# lmr14206.net
KiCad netlist of a schematic drawn in EAGLE
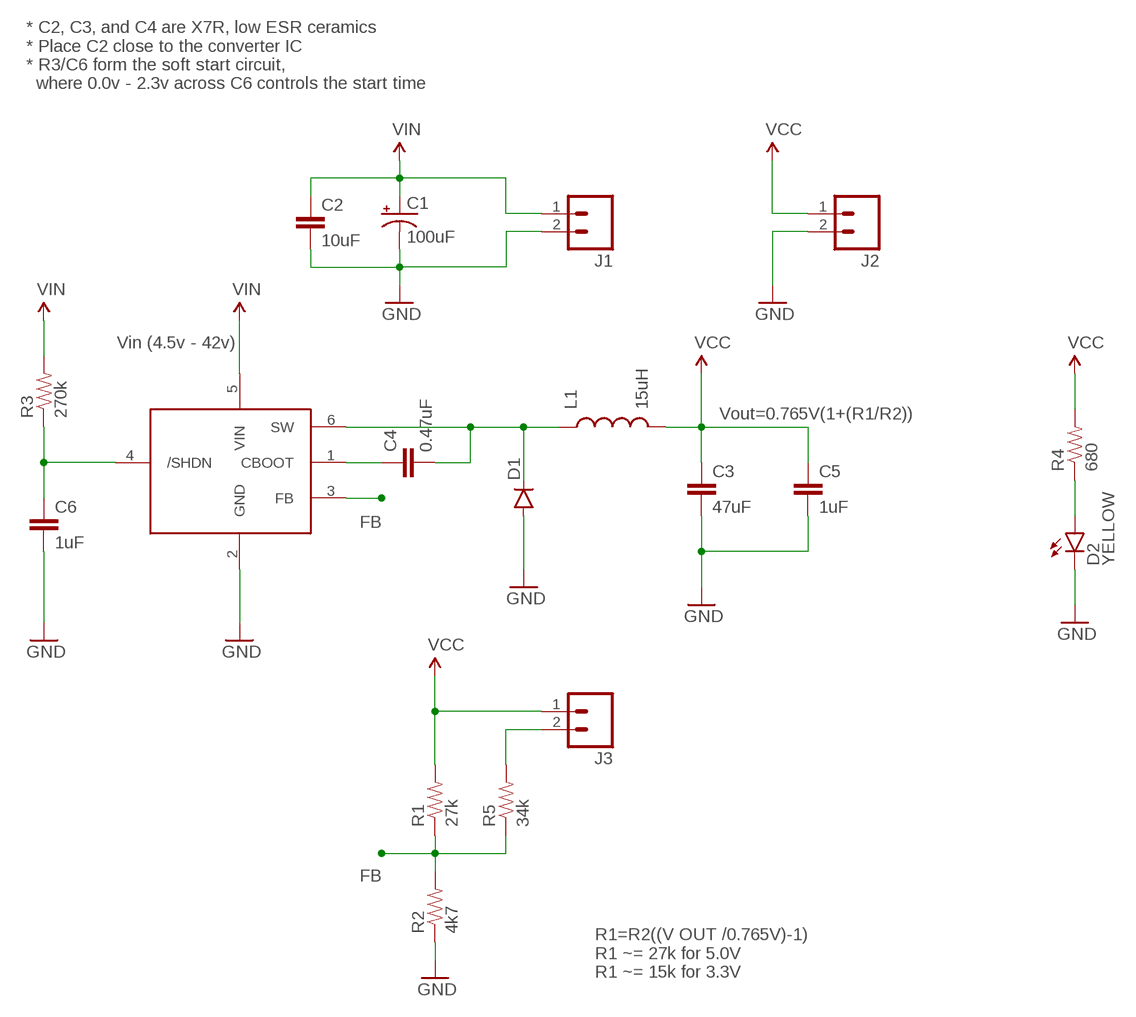
[diagram p0: schematic, sheet 1]

(export (version "E")
  (design (tool "Eeschema 10.0.6"))
  (components
    (comp (ref "C1")
      (value "100uF")
      (footprint "eagle-import:PANASONIC_C")
      (libsource (lib "eagle-import") (part "CAP_POLC"))
    )
    (comp (ref "C2")
      (value "10uF")
      (footprint "eagle-import:0805-CAP")
      (libsource (lib "eagle-import") (part "1UF-25V-10%(0805){dblquote}"))
    )
    (comp (ref "C3")
      (value "47uF")
      (footprint "eagle-import:1210")
      (libsource (lib "eagle-import") (part "100UF6.3V20%(1210)"))
    )
    (comp (ref "C4")
      (value "0.47uF")
      (footprint "eagle-import:0805-CAP")
      (libsource (lib "eagle-import") (part "1UF-25V-10%(0805){dblquote}"))
    )
    (comp (ref "C5")
      (value "1uF")
      (footprint "eagle-import:0805-CAP")
      (libsource (lib "eagle-import") (part "1UF-25V-10%(0805){dblquote}"))
    )
    (comp (ref "C6")
      (value "1uF")
      (footprint "eagle-import:0805-CAP")
      (libsource (lib "eagle-import") (part "1UF-25V-10%(0805){dblquote}"))
    )
    (comp (ref "D1")
      (value "DIODESMB")
      (footprint "eagle-import:SMB-DIODE")
      (libsource (lib "eagle-import") (part "DIODESMB"))
    )
    (comp (ref "D2")
      (value "YELLOW")
      (footprint "eagle-import:LED-1206")
      (libsource (lib "eagle-import") (part "LED-YELLOW1206"))
    )
    (comp (ref "J1")
      (value "M02JST-PTH-VERT")
      (footprint "eagle-import:JST-2-PTH-VERT")
      (libsource (lib "eagle-import") (part "M02JST-PTH-VERT"))
    )
    (comp (ref "J2")
      (value "M02PTH")
      (footprint "eagle-import:1X02")
      (libsource (lib "eagle-import") (part "M02PTH"))
    )
    (comp (ref "J3")
      (value "M02PTH")
      (footprint "eagle-import:1X02")
      (libsource (lib "eagle-import") (part "M02PTH"))
    )
    (comp (ref "L1")
      (value "15uH")
      (footprint "eagle-import:INDUCTOR-1206")
      (libsource (lib "eagle-import") (part "INDUCTORH1206"))
    )
    (comp (ref "R1")
      (value "27k")
      (footprint "eagle-import:0805")
      (libsource (lib "eagle-import") (part "0.75OHM-1/4W-1%(0805)"))
    )
    (comp (ref "R2")
      (value "4k7")
      (footprint "eagle-import:0805")
      (libsource (lib "eagle-import") (part "0.75OHM-1/4W-1%(0805)"))
    )
    (comp (ref "R3")
      (value "270k")
      (footprint "eagle-import:0805")
      (libsource (lib "eagle-import") (part "0.75OHM-1/4W-1%(0805)"))
    )
    (comp (ref "R4")
      (value "680")
      (footprint "eagle-import:0805")
      (libsource (lib "eagle-import") (part "0.3OHM-1/8W-1%(0805)"))
    )
    (comp (ref "R5")
      (value "34k")
      (footprint "eagle-import:0805")
      (libsource (lib "eagle-import") (part "0.75OHM-1/4W-1%(0805)"))
    )
    (comp (ref "U$1")
      (value "LMR14206TSOT-6")
      (footprint "eagle-import:TSOT-6")
      (libsource (lib "eagle-import") (part "LMR14206TSOT-6"))
    )
  )
  (nets
    (net (code "1") (name "/FB") (class "Default")
      (node (ref "R1") (pin "1") (pinfunction "1_1") (pintype "passive"))
      (node (ref "R2") (pin "2") (pinfunction "2_2") (pintype "passive"))
      (node (ref "R5") (pin "1") (pinfunction "1_1") (pintype "passive"))
      (node (ref "U$1") (pin "3") (pinfunction "FB_3") (pintype "bidirectional"))
    )
    (net (code "2") (name "GND") (class "Default")
      (node (ref "C1") (pin "-") (pinfunction "-_-") (pintype "passive"))
      (node (ref "C2") (pin "2") (pinfunction "2_2") (pintype "passive"))
      (node (ref "C3") (pin "2") (pinfunction "2_2") (pintype "passive"))
      (node (ref "C5") (pin "2") (pinfunction "2_2") (pintype "passive"))
      (node (ref "C6") (pin "2") (pinfunction "2_2") (pintype "passive"))
      (node (ref "D1") (pin "A") (pinfunction "A_A") (pintype "passive"))
      (node (ref "D2") (pin "C") (pinfunction "C_C") (pintype "passive"))
      (node (ref "J1") (pin "2") (pinfunction "2_2") (pintype "passive"))
      (node (ref "J2") (pin "2") (pinfunction "2_2") (pintype "passive"))
      (node (ref "R2") (pin "1") (pinfunction "1_1") (pintype "passive"))
      (node (ref "U$1") (pin "2") (pinfunction "GND_2") (pintype "bidirectional"))
    )
    (net (code "3") (name "Net-(D2-PadA)") (class "Default")
      (node (ref "D2") (pin "A") (pinfunction "A_A") (pintype "passive"))
      (node (ref "R4") (pin "1") (pinfunction "1_1") (pintype "passive"))
    )
    (net (code "4") (name "Net-(J3-Pad2)") (class "Default")
      (node (ref "J3") (pin "2") (pinfunction "2_2") (pintype "passive"))
      (node (ref "R5") (pin "2") (pinfunction "2_2") (pintype "passive"))
    )
    (net (code "5") (name "Net-(L1-1)") (class "Default")
      (node (ref "C4") (pin "2") (pinfunction "2_2") (pintype "passive"))
      (node (ref "D1") (pin "C") (pinfunction "C_C") (pintype "passive"))
      (node (ref "L1") (pin "P$1") (pinfunction "1_P$1") (pintype "passive"))
      (node (ref "U$1") (pin "6") (pinfunction "SW_6") (pintype "bidirectional"))
    )
    (net (code "6") (name "Net-(U$1-CBOOT)") (class "Default")
      (node (ref "C4") (pin "1") (pinfunction "1_1") (pintype "passive"))
      (node (ref "U$1") (pin "1") (pinfunction "CBOOT_1") (pintype "bidirectional"))
    )
    (net (code "7") (name "Net-(U$1-{slash}SHDN)") (class "Default")
      (node (ref "C6") (pin "1") (pinfunction "1_1") (pintype "passive"))
      (node (ref "R3") (pin "1") (pinfunction "1_1") (pintype "passive"))
      (node (ref "U$1") (pin "4") (pinfunction "/SHDN_4") (pintype "bidirectional"))
    )
    (net (code "8") (name "VCC") (class "Default")
      (node (ref "C3") (pin "1") (pinfunction "1_1") (pintype "passive"))
      (node (ref "C5") (pin "1") (pinfunction "1_1") (pintype "passive"))
      (node (ref "J2") (pin "1") (pinfunction "1_1") (pintype "passive"))
      (node (ref "J3") (pin "1") (pinfunction "1_1") (pintype "passive"))
      (node (ref "L1") (pin "P$2") (pinfunction "2_P$2") (pintype "passive"))
      (node (ref "R1") (pin "2") (pinfunction "2_2") (pintype "passive"))
      (node (ref "R4") (pin "2") (pinfunction "2_2") (pintype "passive"))
    )
    (net (code "9") (name "VIN") (class "Default")
      (node (ref "C1") (pin "+") (pinfunction "+_+") (pintype "passive"))
      (node (ref "C2") (pin "1") (pinfunction "1_1") (pintype "passive"))
      (node (ref "J1") (pin "1") (pinfunction "1_1") (pintype "passive"))
      (node (ref "R3") (pin "2") (pinfunction "2_2") (pintype "passive"))
      (node (ref "U$1") (pin "5") (pinfunction "VIN_5") (pintype "bidirectional"))
    )
  )
)
